# SpheroRemote_Version2.net
KiCad netlist of a schematic drawn in EAGLE
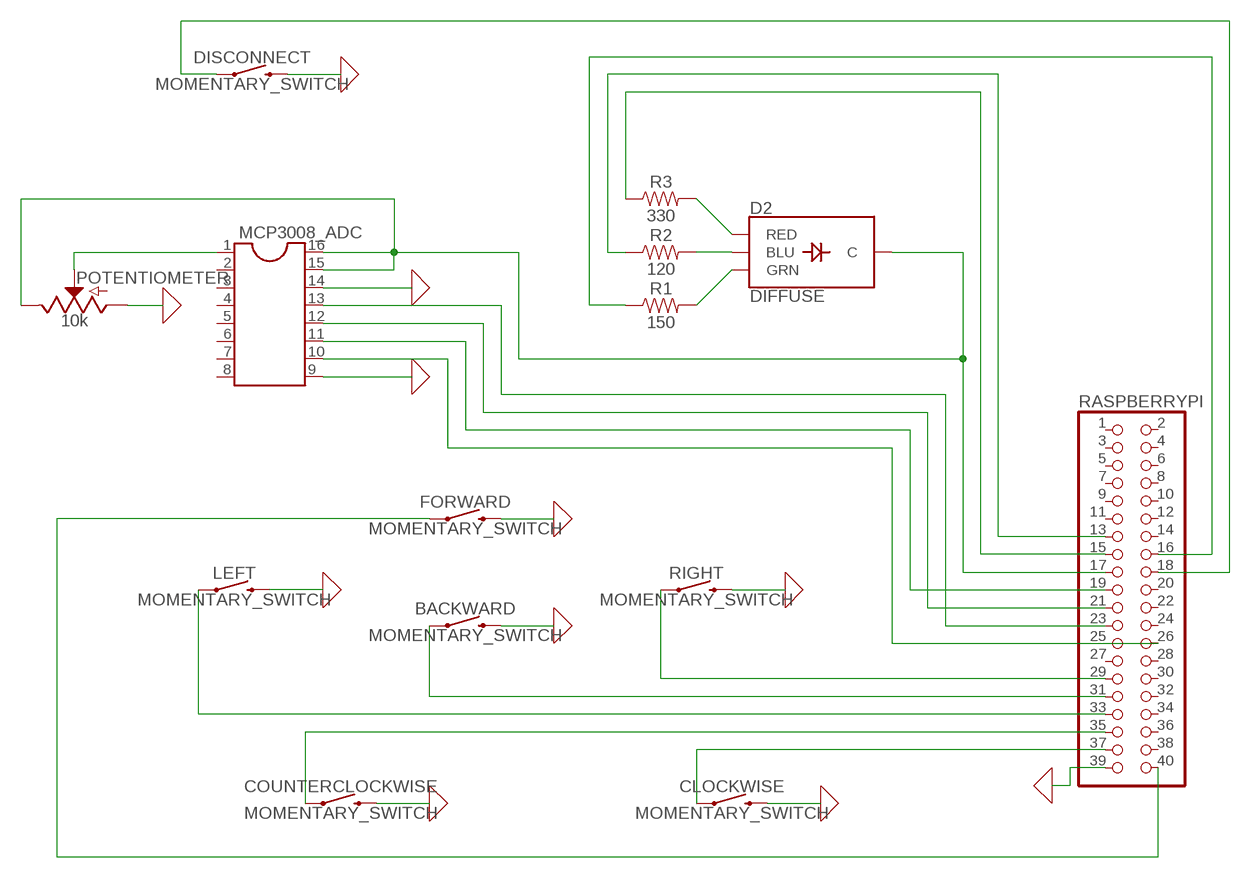
[diagram p0: schematic, sheet 1]

(export (version "E")
  (design (tool "Eeschema 10.0.6"))
  (components
    (comp (ref "BACKWARD")
      (value "MOMENTARY_SWITCH")
      (footprint "eagle-import:TACTILE_SWITCH_PTH_12MM")
      (libsource (lib "eagle-import") (part "MOMENTARY-SWITCH-SPST-PTH-12MM"))
    )
    (comp (ref "CLOCKWISE")
      (value "MOMENTARY_SWITCH")
      (footprint "eagle-import:TACTILE_SWITCH_PTH_12MM")
      (libsource (lib "eagle-import") (part "MOMENTARY-SWITCH-SPST-PTH-12MM"))
    )
    (comp (ref "COUNTERCLOCKWISE")
      (value "MOMENTARY_SWITCH")
      (footprint "eagle-import:TACTILE_SWITCH_PTH_12MM")
      (libsource (lib "eagle-import") (part "MOMENTARY-SWITCH-SPST-PTH-12MM"))
    )
    (comp (ref "D2")
      (value "DIFFUSE")
      (footprint "eagle-import:LED-RGB-THRU")
      (libsource (lib "eagle-import") (part "LED-RGB-CCDIFFUSE"))
    )
    (comp (ref "DISCONNECT")
      (value "MOMENTARY_SWITCH")
      (footprint "eagle-import:TACTILE_SWITCH_PTH_12MM")
      (libsource (lib "eagle-import") (part "MOMENTARY-SWITCH-SPST-PTH-12MM"))
    )
    (comp (ref "FORWARD")
      (value "MOMENTARY_SWITCH")
      (footprint "eagle-import:TACTILE_SWITCH_PTH_12MM")
      (libsource (lib "eagle-import") (part "MOMENTARY-SWITCH-SPST-PTH-12MM"))
    )
    (comp (ref "LEFT")
      (value "MOMENTARY_SWITCH")
      (footprint "eagle-import:TACTILE_SWITCH_PTH_12MM")
      (libsource (lib "eagle-import") (part "MOMENTARY-SWITCH-SPST-PTH-12MM"))
    )
    (comp (ref "MCP3008_ADC")
      (value "DIL16")
      (footprint "eagle-import:DIL16")
      (fields (field (name "SPICEPREFIX") "X"))
      (libsource (lib "eagle-import") (part "DIL16"))
    )
    (comp (ref "POTENTIOMETER")
      (value "10k")
      (footprint "eagle-import:POT-PTH-ALPS-KIT")
      (libsource (lib "eagle-import") (part "POTENTIOMETER-PTH-9MM-1/20W-20%-KIT"))
    )
    (comp (ref "R1")
      (value "150")
      (footprint "eagle-import:AXIAL-0.3")
      (libsource (lib "eagle-import") (part "330OHM-HORIZ-1/10W-5%"))
    )
    (comp (ref "R2")
      (value "120")
      (footprint "eagle-import:AXIAL-0.3")
      (libsource (lib "eagle-import") (part "330OHM-HORIZ-1/10W-5%"))
    )
    (comp (ref "R3")
      (value "330")
      (footprint "eagle-import:AXIAL-0.3")
      (libsource (lib "eagle-import") (part "330OHM-HORIZ-1/10W-5%"))
    )
    (comp (ref "RASPBERRYPI")
      (value "PINHD-2X20")
      (footprint "eagle-import:2X20")
      (libsource (lib "eagle-import") (part "PINHD-2X20"))
    )
    (comp (ref "RIGHT")
      (value "MOMENTARY_SWITCH")
      (footprint "eagle-import:TACTILE_SWITCH_PTH_12MM")
      (libsource (lib "eagle-import") (part "MOMENTARY-SWITCH-SPST-PTH-12MM"))
    )
  )
  (nets
    (net (code "1") (name "GND") (class "Default")
      (node (ref "BACKWARD") (pin "3") (pinfunction "2_3") (pintype "passive"))
      (node (ref "CLOCKWISE") (pin "3") (pinfunction "2_3") (pintype "passive"))
      (node (ref "COUNTERCLOCKWISE") (pin "3") (pinfunction "2_3") (pintype "passive"))
      (node (ref "DISCONNECT") (pin "3") (pinfunction "2_3") (pintype "passive"))
      (node (ref "FORWARD") (pin "3") (pinfunction "2_3") (pintype "passive"))
      (node (ref "LEFT") (pin "3") (pinfunction "2_3") (pintype "passive"))
      (node (ref "MCP3008_ADC") (pin "14") (pinfunction "14_14") (pintype "passive"))
      (node (ref "MCP3008_ADC") (pin "9") (pinfunction "9_9") (pintype "passive"))
      (node (ref "POTENTIOMETER") (pin "P$3") (pinfunction "A_P$3") (pintype "passive"))
      (node (ref "RASPBERRYPI") (pin "39") (pinfunction "39_39") (pintype "passive"))
      (node (ref "RIGHT") (pin "3") (pinfunction "2_3") (pintype "passive"))
    )
    (net (code "2") (name "Net-(BACKWARD-Pad1)") (class "Default")
      (node (ref "BACKWARD") (pin "1") (pinfunction "1_1") (pintype "passive"))
      (node (ref "RASPBERRYPI") (pin "31") (pinfunction "31_31") (pintype "passive"))
    )
    (net (code "3") (name "Net-(CLOCKWISE-Pad1)") (class "Default")
      (node (ref "CLOCKWISE") (pin "1") (pinfunction "1_1") (pintype "passive"))
      (node (ref "RASPBERRYPI") (pin "37") (pinfunction "37_37") (pintype "passive"))
    )
    (net (code "4") (name "Net-(COUNTERCLOCKWISE-Pad1)") (class "Default")
      (node (ref "COUNTERCLOCKWISE") (pin "1") (pinfunction "1_1") (pintype "passive"))
      (node (ref "RASPBERRYPI") (pin "35") (pinfunction "35_35") (pintype "passive"))
    )
    (net (code "5") (name "Net-(D2-BLU)") (class "Default")
      (node (ref "D2") (pin "4") (pinfunction "BLU_4") (pintype "bidirectional"))
      (node (ref "R2") (pin "P$2") (pinfunction "2_P$2") (pintype "passive"))
    )
    (net (code "6") (name "Net-(D2-C)") (class "Default")
      (node (ref "D2") (pin "2") (pinfunction "C_2") (pintype "bidirectional"))
      (node (ref "MCP3008_ADC") (pin "15") (pinfunction "15_15") (pintype "passive"))
      (node (ref "MCP3008_ADC") (pin "16") (pinfunction "16_16") (pintype "passive"))
      (node (ref "POTENTIOMETER") (pin "P$1") (pinfunction "E_P$1") (pintype "passive"))
      (node (ref "RASPBERRYPI") (pin "17") (pinfunction "17_17") (pintype "passive"))
    )
    (net (code "7") (name "Net-(D2-GRN)") (class "Default")
      (node (ref "D2") (pin "3") (pinfunction "GRN_3") (pintype "bidirectional"))
      (node (ref "R1") (pin "P$2") (pinfunction "2_P$2") (pintype "passive"))
    )
    (net (code "8") (name "Net-(D2-RED)") (class "Default")
      (node (ref "D2") (pin "1") (pinfunction "RED_1") (pintype "bidirectional"))
      (node (ref "R3") (pin "P$2") (pinfunction "2_P$2") (pintype "passive"))
    )
    (net (code "9") (name "Net-(DISCONNECT-Pad1)") (class "Default")
      (node (ref "DISCONNECT") (pin "1") (pinfunction "1_1") (pintype "passive"))
      (node (ref "RASPBERRYPI") (pin "18") (pinfunction "18_18") (pintype "passive"))
    )
    (net (code "10") (name "Net-(FORWARD-Pad1)") (class "Default")
      (node (ref "FORWARD") (pin "1") (pinfunction "1_1") (pintype "passive"))
      (node (ref "RASPBERRYPI") (pin "40") (pinfunction "40_40") (pintype "passive"))
    )
    (net (code "11") (name "Net-(LEFT-Pad1)") (class "Default")
      (node (ref "LEFT") (pin "1") (pinfunction "1_1") (pintype "passive"))
      (node (ref "RASPBERRYPI") (pin "33") (pinfunction "33_33") (pintype "passive"))
    )
    (net (code "12") (name "Net-(MCP3008_ADC-Pad10)") (class "Default")
      (node (ref "MCP3008_ADC") (pin "10") (pinfunction "10_10") (pintype "passive"))
      (node (ref "RASPBERRYPI") (pin "26") (pinfunction "26_26") (pintype "passive"))
    )
    (net (code "13") (name "Net-(MCP3008_ADC-Pad11)") (class "Default")
      (node (ref "MCP3008_ADC") (pin "11") (pinfunction "11_11") (pintype "passive"))
      (node (ref "RASPBERRYPI") (pin "19") (pinfunction "19_19") (pintype "passive"))
    )
    (net (code "14") (name "Net-(MCP3008_ADC-Pad12)") (class "Default")
      (node (ref "MCP3008_ADC") (pin "12") (pinfunction "12_12") (pintype "passive"))
      (node (ref "RASPBERRYPI") (pin "21") (pinfunction "21_21") (pintype "passive"))
    )
    (net (code "15") (name "Net-(MCP3008_ADC-Pad13)") (class "Default")
      (node (ref "MCP3008_ADC") (pin "13") (pinfunction "13_13") (pintype "passive"))
      (node (ref "RASPBERRYPI") (pin "23") (pinfunction "23_23") (pintype "passive"))
    )
    (net (code "16") (name "Net-(POTENTIOMETER-S)") (class "Default")
      (node (ref "MCP3008_ADC") (pin "1") (pinfunction "1_1") (pintype "passive"))
      (node (ref "POTENTIOMETER") (pin "P$2") (pinfunction "S_P$2") (pintype "passive"))
    )
    (net (code "17") (name "Net-(R1-1)") (class "Default")
      (node (ref "R1") (pin "P$1") (pinfunction "1_P$1") (pintype "passive"))
      (node (ref "RASPBERRYPI") (pin "16") (pinfunction "16_16") (pintype "passive"))
    )
    (net (code "18") (name "Net-(R2-1)") (class "Default")
      (node (ref "R2") (pin "P$1") (pinfunction "1_P$1") (pintype "passive"))
      (node (ref "RASPBERRYPI") (pin "13") (pinfunction "13_13") (pintype "passive"))
    )
    (net (code "19") (name "Net-(R3-1)") (class "Default")
      (node (ref "R3") (pin "P$1") (pinfunction "1_P$1") (pintype "passive"))
      (node (ref "RASPBERRYPI") (pin "15") (pinfunction "15_15") (pintype "passive"))
    )
    (net (code "20") (name "Net-(RASPBERRYPI-Pad29)") (class "Default")
      (node (ref "RASPBERRYPI") (pin "29") (pinfunction "29_29") (pintype "passive"))
      (node (ref "RIGHT") (pin "1") (pinfunction "1_1") (pintype "passive"))
    )
    (net (code "21") (name "unconnected-(MCP3008_ADC-Pad2)") (class "Default")
      (node (ref "MCP3008_ADC") (pin "2") (pinfunction "2_2") (pintype "passive"))
    )
    (net (code "22") (name "unconnected-(MCP3008_ADC-Pad3)") (class "Default")
      (node (ref "MCP3008_ADC") (pin "3") (pinfunction "3_3") (pintype "passive"))
    )
    (net (code "23") (name "unconnected-(MCP3008_ADC-Pad4)") (class "Default")
      (node (ref "MCP3008_ADC") (pin "4") (pinfunction "4_4") (pintype "passive"))
    )
    (net (code "24") (name "unconnected-(MCP3008_ADC-Pad5)") (class "Default")
      (node (ref "MCP3008_ADC") (pin "5") (pinfunction "5_5") (pintype "passive"))
    )
    (net (code "25") (name "unconnected-(MCP3008_ADC-Pad6)") (class "Default")
      (node (ref "MCP3008_ADC") (pin "6") (pinfunction "6_6") (pintype "passive"))
    )
    (net (code "26") (name "unconnected-(MCP3008_ADC-Pad7)") (class "Default")
      (node (ref "MCP3008_ADC") (pin "7") (pinfunction "7_7") (pintype "passive"))
    )
    (net (code "27") (name "unconnected-(MCP3008_ADC-Pad8)") (class "Default")
      (node (ref "MCP3008_ADC") (pin "8") (pinfunction "8_8") (pintype "passive"))
    )
    (net (code "28") (name "unconnected-(RASPBERRYPI-Pad1)") (class "Default")
      (node (ref "RASPBERRYPI") (pin "1") (pinfunction "1_1") (pintype "passive"))
    )
    (net (code "29") (name "unconnected-(RASPBERRYPI-Pad2)") (class "Default")
      (node (ref "RASPBERRYPI") (pin "2") (pinfunction "2_2") (pintype "passive"))
    )
    (net (code "30") (name "unconnected-(RASPBERRYPI-Pad3)") (class "Default")
      (node (ref "RASPBERRYPI") (pin "3") (pinfunction "3_3") (pintype "passive"))
    )
    (net (code "31") (name "unconnected-(RASPBERRYPI-Pad4)") (class "Default")
      (node (ref "RASPBERRYPI") (pin "4") (pinfunction "4_4") (pintype "passive"))
    )
    (net (code "32") (name "unconnected-(RASPBERRYPI-Pad5)") (class "Default")
      (node (ref "RASPBERRYPI") (pin "5") (pinfunction "5_5") (pintype "passive"))
    )
    (net (code "33") (name "unconnected-(RASPBERRYPI-Pad6)") (class "Default")
      (node (ref "RASPBERRYPI") (pin "6") (pinfunction "6_6") (pintype "passive"))
    )
    (net (code "34") (name "unconnected-(RASPBERRYPI-Pad7)") (class "Default")
      (node (ref "RASPBERRYPI") (pin "7") (pinfunction "7_7") (pintype "passive"))
    )
    (net (code "35") (name "unconnected-(RASPBERRYPI-Pad8)") (class "Default")
      (node (ref "RASPBERRYPI") (pin "8") (pinfunction "8_8") (pintype "passive"))
    )
    (net (code "36") (name "unconnected-(RASPBERRYPI-Pad9)") (class "Default")
      (node (ref "RASPBERRYPI") (pin "9") (pinfunction "9_9") (pintype "passive"))
    )
    (net (code "37") (name "unconnected-(RASPBERRYPI-Pad10)") (class "Default")
      (node (ref "RASPBERRYPI") (pin "10") (pinfunction "10_10") (pintype "passive"))
    )
    (net (code "38") (name "unconnected-(RASPBERRYPI-Pad11)") (class "Default")
      (node (ref "RASPBERRYPI") (pin "11") (pinfunction "11_11") (pintype "passive"))
    )
    (net (code "39") (name "unconnected-(RASPBERRYPI-Pad12)") (class "Default")
      (node (ref "RASPBERRYPI") (pin "12") (pinfunction "12_12") (pintype "passive"))
    )
    (net (code "40") (name "unconnected-(RASPBERRYPI-Pad14)") (class "Default")
      (node (ref "RASPBERRYPI") (pin "14") (pinfunction "14_14") (pintype "passive"))
    )
    (net (code "41") (name "unconnected-(RASPBERRYPI-Pad20)") (class "Default")
      (node (ref "RASPBERRYPI") (pin "20") (pinfunction "20_20") (pintype "passive"))
    )
    (net (code "42") (name "unconnected-(RASPBERRYPI-Pad22)") (class "Default")
      (node (ref "RASPBERRYPI") (pin "22") (pinfunction "22_22") (pintype "passive"))
    )
    (net (code "43") (name "unconnected-(RASPBERRYPI-Pad24)") (class "Default")
      (node (ref "RASPBERRYPI") (pin "24") (pinfunction "24_24") (pintype "passive"))
    )
    (net (code "44") (name "unconnected-(RASPBERRYPI-Pad25)") (class "Default")
      (node (ref "RASPBERRYPI") (pin "25") (pinfunction "25_25") (pintype "passive"))
    )
    (net (code "45") (name "unconnected-(RASPBERRYPI-Pad27)") (class "Default")
      (node (ref "RASPBERRYPI") (pin "27") (pinfunction "27_27") (pintype "passive"))
    )
    (net (code "46") (name "unconnected-(RASPBERRYPI-Pad28)") (class "Default")
      (node (ref "RASPBERRYPI") (pin "28") (pinfunction "28_28") (pintype "passive"))
    )
    (net (code "47") (name "unconnected-(RASPBERRYPI-Pad30)") (class "Default")
      (node (ref "RASPBERRYPI") (pin "30") (pinfunction "30_30") (pintype "passive"))
    )
    (net (code "48") (name "unconnected-(RASPBERRYPI-Pad32)") (class "Default")
      (node (ref "RASPBERRYPI") (pin "32") (pinfunction "32_32") (pintype "passive"))
    )
    (net (code "49") (name "unconnected-(RASPBERRYPI-Pad34)") (class "Default")
      (node (ref "RASPBERRYPI") (pin "34") (pinfunction "34_34") (pintype "passive"))
    )
    (net (code "50") (name "unconnected-(RASPBERRYPI-Pad36)") (class "Default")
      (node (ref "RASPBERRYPI") (pin "36") (pinfunction "36_36") (pintype "passive"))
    )
    (net (code "51") (name "unconnected-(RASPBERRYPI-Pad38)") (class "Default")
      (node (ref "RASPBERRYPI") (pin "38") (pinfunction "38_38") (pintype "passive"))
    )
  )
)
